# UPA-DIP.net
KiCad netlist of a schematic drawn in Altium Designer
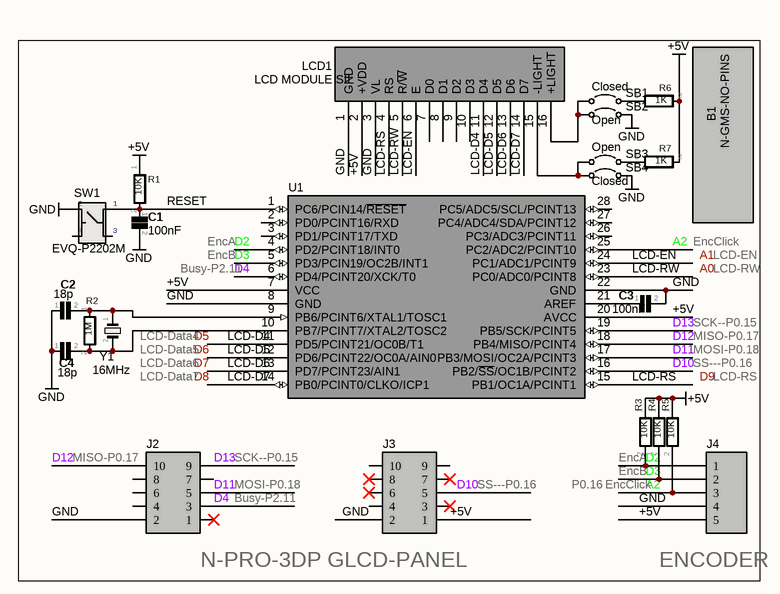
[diagram p0: UPA-DIP.SchDoc]

(export (version "E")
  (design (tool "Eeschema 10.0.6"))
  (components
    (comp (ref "B1")
      (value "N-GMS-NO-PINS")
      (footprint "N-GMS-NO-PINS")
      (libsource (lib "NX2") (part "N-GMS-NO-PINS"))
    )
    (comp (ref "C1")
      (value "100nF")
      (footprint "CK05")
      (description "CAPACITOR")
      (libsource (lib "") (part "C_1"))
    )
    (comp (ref "C2")
      (value "18p")
      (footprint "CK05")
      (description "CAPACITOR")
      (libsource (lib "NX1") (part "C"))
    )
    (comp (ref "C3")
      (value "100nF")
      (footprint "CK05")
      (description "CAPACITOR")
      (libsource (lib "NX1") (part "C"))
    )
    (comp (ref "C4")
      (value "18p")
      (footprint "CK05")
      (description "CAPACITOR")
      (libsource (lib "NX1") (part "C"))
    )
    (comp (ref "J2")
      (value "Header 5X2")
      (footprint "ML10")
      (description "Header, 5-Pin, Dual row")
      (libsource (lib "NX1") (part "Header 5X2"))
    )
    (comp (ref "J3")
      (value "Header 5X2")
      (footprint "ML10")
      (description "Header, 5-Pin, Dual row")
      (libsource (lib "NX1") (part "Header 5X2"))
    )
    (comp (ref "J4") (value "HEADER_5") (footprint "1X05") (libsource (lib "NX1") (part "HEADER_5")))
    (comp (ref "LCD1")
      (value "LCD MODULE SIL")
      (footprint "1X16-FEMALE")
      (description "LCD MODULE SINGLE IN LINE")
      (libsource (lib "NX1") (part "LCD MODULE SIL_1"))
    )
    (comp (ref "R1")
      (value "10K")
      (footprint "RS-2,5")
      (description "RESISTOR")
      (libsource (lib "NX2") (part "R"))
    )
    (comp (ref "R2")
      (value "1M")
      (footprint "RS-2,5")
      (description "RESISTOR")
      (libsource (lib "NX2") (part "R"))
    )
    (comp (ref "R3")
      (value "10K")
      (footprint "RS-2,5")
      (description "RESISTOR")
      (libsource (lib "NX2") (part "R"))
    )
    (comp (ref "R4")
      (value "10K")
      (footprint "RS-2,5")
      (description "RESISTOR")
      (libsource (lib "NX2") (part "R"))
    )
    (comp (ref "R5")
      (value "10K")
      (footprint "RS-2,5")
      (description "RESISTOR")
      (libsource (lib "NX2") (part "R"))
    )
    (comp (ref "R6")
      (value "1Κ")
      (footprint "RS-2,5")
      (description "RESISTOR")
      (libsource (lib "") (part "R_1"))
    )
    (comp (ref "R7")
      (value "1Κ")
      (footprint "RS-2,5")
      (description "RESISTOR")
      (libsource (lib "") (part "R_1"))
    )
    (comp (ref "SB1")
      (value "Closed")
      (footprint "0603_JUMPER")
      (description "Circuit Breaker")
      (fields (field (name "PUBLISHER") "Altium Limited"))
      (libsource (lib "NX1") (part "HEADER2_CIRCUIT_BRAKER"))
    )
    (comp (ref "SB2")
      (value "Open")
      (footprint "0603_JUMPER")
      (description "Circuit Breaker")
      (fields (field (name "PUBLISHER") "Altium Limited"))
      (libsource (lib "NX1") (part "HEADER2_CIRCUIT_BRAKER"))
    )
    (comp (ref "SB3")
      (value "Open")
      (footprint "0603_JUMPER")
      (description "Circuit Breaker")
      (fields (field (name "PUBLISHER") "Altium Limited"))
      (libsource (lib "NX1") (part "HEADER2_CIRCUIT_BRAKER"))
    )
    (comp (ref "SB4")
      (value "Closed")
      (footprint "0603_JUMPER")
      (description "Circuit Breaker")
      (fields (field (name "PUBLISHER") "Altium Limited"))
      (libsource (lib "NX1") (part "HEADER2_CIRCUIT_BRAKER"))
    )
    (comp (ref "SW1")
      (value "EVQ-P2202M")
      (footprint "BUTTON_6X6mm")
      (description "BUTTON TACTILE")
      (libsource (lib "NX1") (part "BUTTON_TACT"))
    )
    (comp (ref "U1")
      (value "ATmega328PU")
      (footprint "DIL28-300wSOCKET")
      (description "8-Bit AVR Microcontroller with 32K Bytes of In-System Programmable Flash Memory")
      (fields (field (name "PUBLISHER") "Altium Limited"))
      (libsource (lib "NX1") (part "ATmega48/88/168"))
    )
    (comp (ref "Y1")
      (value "16MHz")
      (footprint "HC49U-V")
      (description "CRYSTAL")
      (libsource (lib "NX2") (part "XTAL"))
    )
  )
  (nets
    (net (code "1") (name "+5V") (class "Default")
      (node (ref "J3") (pin "1") (pinfunction "1_1") (pintype "passive"))
      (node (ref "J4") (pin "5") (pinfunction "5_5") (pintype "passive"))
      (node (ref "LCD1") (pin "2") (pinfunction "+VDD_2") (pintype "passive"))
      (node (ref "R1") (pin "1") (pinfunction "1_1") (pintype "passive"))
      (node (ref "R3") (pin "1") (pinfunction "1_1") (pintype "passive"))
      (node (ref "R4") (pin "1") (pinfunction "1_1") (pintype "passive"))
      (node (ref "R5") (pin "1") (pinfunction "1_1") (pintype "passive"))
      (node (ref "R6") (pin "2") (pinfunction "2_2") (pintype "passive"))
      (node (ref "R7") (pin "2") (pinfunction "2_2") (pintype "passive"))
      (node (ref "U1") (pin "20") (pinfunction "AVCC_20") (pintype "tri_state"))
      (node (ref "U1") (pin "7") (pinfunction "VCC_7") (pintype "passive"))
    )
    (net (code "4") (name "/A2") (class "Default")
      (node (ref "J4") (pin "3") (pinfunction "3_3") (pintype "passive"))
      (node (ref "R5") (pin "2") (pinfunction "2_2") (pintype "passive"))
      (node (ref "U1") (pin "25") (pinfunction "PC2/ADC2/PCINT10_25") (pintype "bidirectional"))
    )
    (net (code "5") (name "/D2") (class "Default")
      (node (ref "J4") (pin "1") (pinfunction "1_1") (pintype "passive"))
      (node (ref "R3") (pin "2") (pinfunction "2_2") (pintype "passive"))
      (node (ref "U1") (pin "4") (pinfunction "PD2/PCINT18/INT0_4") (pintype "bidirectional"))
    )
    (net (code "6") (name "/D3") (class "Default")
      (node (ref "J4") (pin "2") (pinfunction "2_2") (pintype "passive"))
      (node (ref "R4") (pin "2") (pinfunction "2_2") (pintype "passive"))
      (node (ref "U1") (pin "5") (pinfunction "PD3/PCIN19/OC2B/INT1_5") (pintype "bidirectional"))
    )
    (net (code "7") (name "/D4") (class "Default")
      (node (ref "J2") (pin "3") (pinfunction "3_3") (pintype "passive"))
      (node (ref "U1") (pin "6") (pinfunction "PD4/PCINT20/XCK/T0_6") (pintype "bidirectional"))
    )
    (net (code "13") (name "/D10") (class "Default")
      (node (ref "J3") (pin "5") (pinfunction "5_5") (pintype "passive"))
      (node (ref "U1") (pin "16") (pinfunction "PB2/~{SS}/OC1B/PCINT2_16") (pintype "bidirectional"))
    )
    (net (code "14") (name "/D11") (class "Default")
      (node (ref "J2") (pin "5") (pinfunction "5_5") (pintype "passive"))
      (node (ref "U1") (pin "17") (pinfunction "PB3/MOSI/OC2A/PCINT3_17") (pintype "bidirectional"))
    )
    (net (code "15") (name "/D12") (class "Default")
      (node (ref "J2") (pin "10") (pinfunction "10_10") (pintype "passive"))
      (node (ref "U1") (pin "18") (pinfunction "PB4/MISO/PCINT4_18") (pintype "bidirectional"))
    )
    (net (code "16") (name "/D13") (class "Default")
      (node (ref "J2") (pin "9") (pinfunction "9_9") (pintype "passive"))
      (node (ref "U1") (pin "19") (pinfunction "PB5/SCK/PCINT5_19") (pintype "bidirectional"))
    )
    (net (code "17") (name "/LCD-D4") (class "Default")
      (node (ref "LCD1") (pin "11") (pinfunction "D4_11") (pintype "passive"))
      (node (ref "U1") (pin "11") (pinfunction "PD5/PCINT21/OC0B/T1_11") (pintype "power_in"))
    )
    (net (code "18") (name "/LCD-D5") (class "Default")
      (node (ref "LCD1") (pin "12") (pinfunction "D5_12") (pintype "passive"))
      (node (ref "U1") (pin "12") (pinfunction "PD6/PCINT22/OC0A/AIN0_12") (pintype "passive"))
    )
    (net (code "19") (name "/LCD-D6") (class "Default")
      (node (ref "LCD1") (pin "13") (pinfunction "D6_13") (pintype "passive"))
      (node (ref "U1") (pin "13") (pinfunction "PD7/PCINT23/AIN1_13") (pintype "passive"))
    )
    (net (code "20") (name "/LCD-D7") (class "Default")
      (node (ref "LCD1") (pin "14") (pinfunction "D7_14") (pintype "passive"))
      (node (ref "U1") (pin "14") (pinfunction "PB0/PCINT0/CLKO/ICP1_14") (pintype "bidirectional"))
    )
    (net (code "21") (name "/LCD-EN") (class "Default")
      (node (ref "LCD1") (pin "6") (pinfunction "E_6") (pintype "passive"))
      (node (ref "U1") (pin "24") (pinfunction "PC1/ADC1/PCINT9_24") (pintype "bidirectional"))
    )
    (net (code "22") (name "/LCD-RS") (class "Default")
      (node (ref "LCD1") (pin "4") (pinfunction "RS_4") (pintype "passive"))
      (node (ref "U1") (pin "15") (pinfunction "PB1/OC1A/PCINT1_15") (pintype "bidirectional"))
    )
    (net (code "23") (name "/LCD-RW") (class "Default")
      (node (ref "LCD1") (pin "5") (pinfunction "R/~{W}_5") (pintype "passive"))
      (node (ref "U1") (pin "23") (pinfunction "PC0/ADC0/PCINT8_23") (pintype "bidirectional"))
    )
    (net (code "24") (name "/RESET") (class "Default")
      (node (ref "C1") (pin "1") (pinfunction "1_1") (pintype "passive"))
      (node (ref "R1") (pin "2") (pinfunction "2_2") (pintype "passive"))
      (node (ref "SW1") (pin "1") (pinfunction "1_1") (pintype "passive"))
      (node (ref "U1") (pin "1") (pinfunction "PC6/PCIN14/~{RESET}_1") (pintype "bidirectional"))
    )
    (net (code "25") (name "GND") (class "Default")
      (node (ref "C1") (pin "2") (pinfunction "2_2") (pintype "passive"))
      (node (ref "C2") (pin "1") (pinfunction "1_1") (pintype "passive"))
      (node (ref "C3") (pin "2") (pinfunction "2_2") (pintype "passive"))
      (node (ref "C4") (pin "1") (pinfunction "1_1") (pintype "passive"))
      (node (ref "J2") (pin "2") (pinfunction "2_2") (pintype "passive"))
      (node (ref "J3") (pin "2") (pinfunction "2_2") (pintype "passive"))
      (node (ref "J4") (pin "4") (pinfunction "4_4") (pintype "passive"))
      (node (ref "LCD1") (pin "1") (pinfunction "GND_1") (pintype "passive"))
      (node (ref "LCD1") (pin "3") (pinfunction "VL_3") (pintype "passive"))
      (node (ref "SB2") (pin "2") (pinfunction "2_2") (pintype "passive"))
      (node (ref "SB4") (pin "2") (pinfunction "2_2") (pintype "passive"))
      (node (ref "SW1") (pin "2") (pinfunction "2_2") (pintype "passive"))
      (node (ref "U1") (pin "22") (pinfunction "GND_22") (pintype "passive"))
      (node (ref "U1") (pin "8") (pinfunction "GND_8") (pintype "passive"))
    )
    (net (code "26") (name "Net-(LCD1-+LIGHT)") (class "Default")
      (node (ref "LCD1") (pin "16") (pinfunction "+LIGHT_16") (pintype "passive"))
      (node (ref "SB1") (pin "1") (pinfunction "1_1") (pintype "passive"))
      (node (ref "SB2") (pin "1") (pinfunction "1_1") (pintype "passive"))
    )
    (net (code "27") (name "Net-(LCD1--LIGHT)") (class "Default")
      (node (ref "LCD1") (pin "15") (pinfunction "-LIGHT_15") (pintype "passive"))
      (node (ref "SB3") (pin "1") (pinfunction "1_1") (pintype "passive"))
      (node (ref "SB4") (pin "1") (pinfunction "1_1") (pintype "passive"))
    )
    (net (code "28") (name "Net-(R6-Pad1)") (class "Default")
      (node (ref "R6") (pin "1") (pinfunction "1_1") (pintype "passive"))
      (node (ref "SB1") (pin "2") (pinfunction "2_2") (pintype "passive"))
    )
    (net (code "29") (name "Net-(R7-Pad1)") (class "Default")
      (node (ref "R7") (pin "1") (pinfunction "1_1") (pintype "passive"))
      (node (ref "SB3") (pin "2") (pinfunction "2_2") (pintype "passive"))
    )
    (net (code "30") (name "Net-(U1-AREF)") (class "Default")
      (node (ref "C3") (pin "1") (pinfunction "1_1") (pintype "passive"))
      (node (ref "U1") (pin "21") (pinfunction "AREF_21") (pintype "passive"))
    )
    (net (code "31") (name "Net-(U1-PB6{slash}PCINT6{slash}XTAL1{slash}TOSC1)") (class "Default")
      (node (ref "C2") (pin "2") (pinfunction "2_2") (pintype "passive"))
      (node (ref "R2") (pin "1") (pinfunction "1_1") (pintype "passive"))
      (node (ref "U1") (pin "9") (pinfunction "PB6/PCINT6/XTAL1/TOSC1_9") (pintype "input"))
      (node (ref "Y1") (pin "1") (pinfunction "1_1") (pintype "passive"))
    )
    (net (code "32") (name "Net-(U1-PB7{slash}PCINT7{slash}XTAL2{slash}TOSC2)") (class "Default")
      (node (ref "C4") (pin "2") (pinfunction "2_2") (pintype "passive"))
      (node (ref "R2") (pin "2") (pinfunction "2_2") (pintype "passive"))
      (node (ref "U1") (pin "10") (pinfunction "PB7/PCINT7/XTAL2/TOSC2_10") (pintype "power_in"))
      (node (ref "Y1") (pin "2") (pinfunction "2_2") (pintype "passive"))
    )
    (net (code "33") (name "unconnected-(J2-Pad1)") (class "Default")
      (node (ref "J2") (pin "1") (pinfunction "1_1") (pintype "passive+no_connect"))
    )
    (net (code "34") (name "unconnected-(J2-Pad4)") (class "Default")
      (node (ref "J2") (pin "4") (pinfunction "4_4") (pintype "passive"))
    )
    (net (code "35") (name "unconnected-(J2-Pad6)") (class "Default")
      (node (ref "J2") (pin "6") (pinfunction "6_6") (pintype "passive"))
    )
    (net (code "36") (name "unconnected-(J2-Pad7)") (class "Default")
      (node (ref "J2") (pin "7") (pinfunction "7_7") (pintype "passive"))
    )
    (net (code "37") (name "unconnected-(J2-Pad8)") (class "Default")
      (node (ref "J2") (pin "8") (pinfunction "8_8") (pintype "passive"))
    )
    (net (code "38") (name "unconnected-(J3-Pad3)") (class "Default")
      (node (ref "J3") (pin "3") (pinfunction "3_3") (pintype "passive+no_connect"))
    )
    (net (code "39") (name "unconnected-(J3-Pad4)") (class "Default")
      (node (ref "J3") (pin "4") (pinfunction "4_4") (pintype "passive"))
    )
    (net (code "40") (name "unconnected-(J3-Pad6)") (class "Default")
      (node (ref "J3") (pin "6") (pinfunction "6_6") (pintype "passive+no_connect"))
    )
    (net (code "41") (name "unconnected-(J3-Pad7)") (class "Default")
      (node (ref "J3") (pin "7") (pinfunction "7_7") (pintype "passive+no_connect"))
    )
    (net (code "42") (name "unconnected-(J3-Pad8)") (class "Default")
      (node (ref "J3") (pin "8") (pinfunction "8_8") (pintype "passive+no_connect"))
    )
    (net (code "43") (name "unconnected-(J3-Pad9)") (class "Default")
      (node (ref "J3") (pin "9") (pinfunction "9_9") (pintype "passive"))
    )
    (net (code "44") (name "unconnected-(J3-Pad10)") (class "Default")
      (node (ref "J3") (pin "10") (pinfunction "10_10") (pintype "passive"))
    )
    (net (code "45") (name "unconnected-(LCD1-D0-Pad7)") (class "Default")
      (node (ref "LCD1") (pin "7") (pinfunction "D0_7") (pintype "passive"))
    )
    (net (code "46") (name "unconnected-(LCD1-D1-Pad8)") (class "Default")
      (node (ref "LCD1") (pin "8") (pinfunction "D1_8") (pintype "passive"))
    )
    (net (code "47") (name "unconnected-(LCD1-D2-Pad9)") (class "Default")
      (node (ref "LCD1") (pin "9") (pinfunction "D2_9") (pintype "passive"))
    )
    (net (code "48") (name "unconnected-(LCD1-D3-Pad10)") (class "Default")
      (node (ref "LCD1") (pin "10") (pinfunction "D3_10") (pintype "passive"))
    )
    (net (code "49") (name "unconnected-(SW1-Pad3)") (class "Default")
      (node (ref "SW1") (pin "3") (pinfunction "3_3") (pintype "passive"))
    )
    (net (code "50") (name "unconnected-(SW1-Pad4)") (class "Default")
      (node (ref "SW1") (pin "4") (pinfunction "4_4") (pintype "passive"))
    )
    (net (code "51") (name "unconnected-(U1-PC3{slash}ADC3{slash}PCINT11-Pad26)") (class "Default")
      (node (ref "U1") (pin "26") (pinfunction "PC3/ADC3/PCINT11_26") (pintype "bidirectional"))
    )
    (net (code "52") (name "unconnected-(U1-PC4{slash}ADC4{slash}SDA{slash}PCINT12-Pad27)") (class "Default")
      (node (ref "U1") (pin "27") (pinfunction "PC4/ADC4/SDA/PCINT12_27") (pintype "bidirectional"))
    )
    (net (code "53") (name "unconnected-(U1-PC5{slash}ADC5{slash}SCL{slash}PCINT13-Pad28)") (class "Default")
      (node (ref "U1") (pin "28") (pinfunction "PC5/ADC5/SCL/PCINT13_28") (pintype "bidirectional"))
    )
    (net (code "54") (name "unconnected-(U1-PD0{slash}PCINT16{slash}RXD-Pad2)") (class "Default")
      (node (ref "U1") (pin "2") (pinfunction "PD0/PCINT16/RXD_2") (pintype "bidirectional"))
    )
    (net (code "55") (name "unconnected-(U1-PD1{slash}PCINT17{slash}TXD-Pad3)") (class "Default")
      (node (ref "U1") (pin "3") (pinfunction "PD1/PCINT17/TXD_3") (pintype "bidirectional"))
    )
  )
)
